# 03_power.net
KiCad netlist of a schematic drawn in Altium Designer
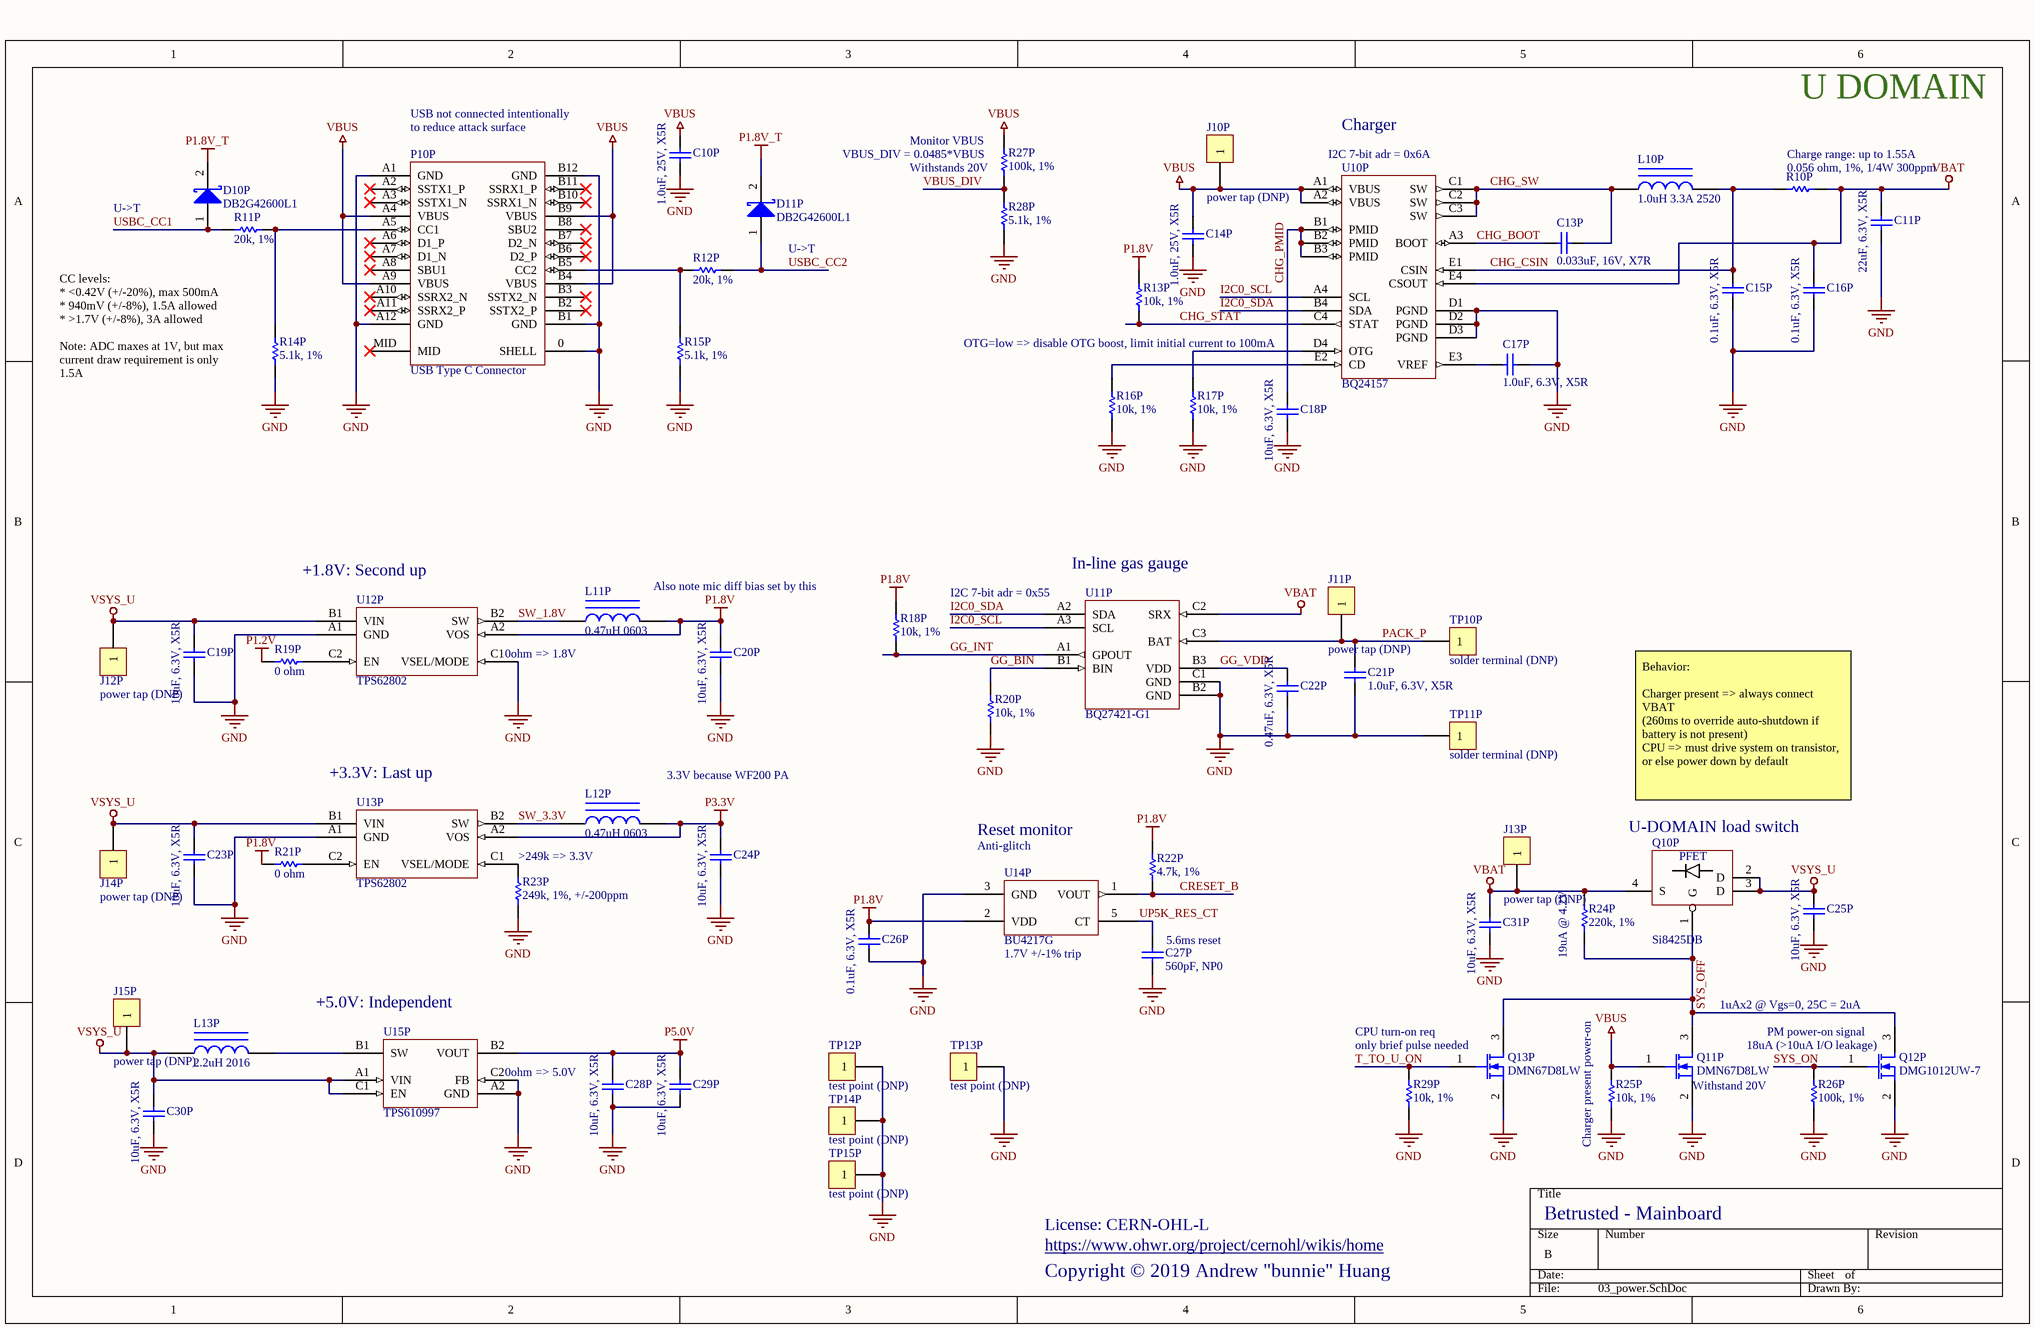
[diagram p0: 03_power.SchDoc]

(export (version "E")
  (design (tool "Eeschema 10.0.6"))
  (components
    (comp (ref "C10P")
      (value "1.0uF, 25V, X5R")
      (footprint "B_CAP0603")
      (description "Capacitor (Semiconductor SIM Model)")
      (fields (field (name "MPN") "CL10A105KA8NNNC"))
      (libsource (lib "Miscellaneous Devices") (part "Cap Semi"))
    )
    (comp (ref "C11P")
      (value "22uF, 6.3V, X5R")
      (footprint "B_CAP0805")
      (description "Capacitor (Semiconductor SIM Model)")
      (fields (field (name "MPN") "CL21A226MQQNNNE"))
      (libsource (lib "Miscellaneous Devices") (part "Cap Semi"))
    )
    (comp (ref "C13P")
      (value "0.033uF, 16V, X7R")
      (footprint "B_RES0402")
      (description "Capacitor (Semiconductor SIM Model)")
      (fields (field (name "MPN") "CL05B333KO5NNNC"))
      (libsource (lib "Miscellaneous Devices") (part "Cap Semi"))
    )
    (comp (ref "C14P")
      (value "1.0uF, 25V, X5R")
      (footprint "B_CAP0603")
      (description "Capacitor (Semiconductor SIM Model)")
      (fields (field (name "MPN") "CL10A105KA8NNNC"))
      (libsource (lib "Miscellaneous Devices") (part "Cap Semi"))
    )
    (comp (ref "C15P")
      (value "0.1uF, 6.3V, X5R")
      (footprint "B_CAP0201")
      (description "Capacitor (Semiconductor SIM Model)")
      (fields (field (name "MPN") "CL03A104KQ3NNNC"))
      (libsource (lib "Miscellaneous Devices") (part "Cap Semi"))
    )
    (comp (ref "C16P")
      (value "0.1uF, 6.3V, X5R")
      (footprint "B_CAP0201")
      (description "Capacitor (Semiconductor SIM Model)")
      (fields (field (name "MPN") "CL03A104KQ3NNNC"))
      (libsource (lib "Miscellaneous Devices") (part "Cap Semi"))
    )
    (comp (ref "C17P")
      (value "1.0uF, 6.3V, X5R")
      (footprint "B_CAP0201")
      (description "Capacitor (Semiconductor SIM Model)")
      (fields (field (name "MPN") "GRM033R60J105MEA2D"))
      (libsource (lib "Miscellaneous Devices") (part "Cap Semi"))
    )
    (comp (ref "C18P")
      (value "10uF, 6.3V, X5R")
      (footprint "B_CAP0603")
      (description "Capacitor (Semiconductor SIM Model)")
      (fields (field (name "MPN") "CL10A106MQ8NNNC"))
      (libsource (lib "Miscellaneous Devices") (part "Cap Semi"))
    )
    (comp (ref "C19P")
      (value "10uF, 6.3V, X5R")
      (footprint "B_CAP0603")
      (description "Capacitor (Semiconductor SIM Model)")
      (fields (field (name "MPN") "CL10A106MQ8NNNC"))
      (libsource (lib "Miscellaneous Devices") (part "Cap Semi"))
    )
    (comp (ref "C20P")
      (value "10uF, 6.3V, X5R")
      (footprint "B_CAP0603")
      (description "Capacitor (Semiconductor SIM Model)")
      (fields (field (name "MPN") "CL10A106MQ8NNNC"))
      (libsource (lib "Miscellaneous Devices") (part "Cap Semi"))
    )
    (comp (ref "C21P")
      (value "1.0uF, 6.3V, X5R")
      (footprint "B_CAP0201")
      (description "Capacitor (Semiconductor SIM Model)")
      (fields (field (name "MPN") "GRM033R60J105MEA2D"))
      (libsource (lib "Miscellaneous Devices") (part "Cap Semi"))
    )
    (comp (ref "C22P")
      (value "0.47uF, 6.3V, X5R")
      (footprint "B_CAP0201")
      (description "Capacitor (Semiconductor SIM Model)")
      (fields (field (name "MPN") "CL03A474KQ3NNNH"))
      (libsource (lib "Miscellaneous Devices") (part "Cap Semi"))
    )
    (comp (ref "C23P")
      (value "10uF, 6.3V, X5R")
      (footprint "B_CAP0603")
      (description "Capacitor (Semiconductor SIM Model)")
      (fields (field (name "MPN") "CL10A106MQ8NNNC"))
      (libsource (lib "Miscellaneous Devices") (part "Cap Semi"))
    )
    (comp (ref "C24P")
      (value "10uF, 6.3V, X5R")
      (footprint "B_CAP0603")
      (description "Capacitor (Semiconductor SIM Model)")
      (fields (field (name "MPN") "CL10A106MQ8NNNC"))
      (libsource (lib "Miscellaneous Devices") (part "Cap Semi"))
    )
    (comp (ref "C25P")
      (value "10uF, 6.3V, X5R")
      (footprint "B_CAP0603")
      (description "Capacitor (Semiconductor SIM Model)")
      (fields (field (name "MPN") "CL10A106MQ8NNNC"))
      (libsource (lib "Miscellaneous Devices") (part "Cap Semi"))
    )
    (comp (ref "C26P")
      (value "0.1uF, 6.3V, X5R")
      (footprint "B_CAP0201")
      (description "Capacitor (Semiconductor SIM Model)")
      (fields (field (name "MPN") "CL03A104KQ3NNNC"))
      (libsource (lib "Miscellaneous Devices") (part "Cap Semi"))
    )
    (comp (ref "C27P")
      (value "560pF, NP0")
      (footprint "B_RES0201")
      (description "Capacitor (Semiconductor SIM Model)")
      (fields (field (name "MPN") "GRM0335C1E561JA01D"))
      (libsource (lib "Miscellaneous Devices") (part "Cap Semi"))
    )
    (comp (ref "C28P")
      (value "10uF, 6.3V, X5R")
      (footprint "B_CAP0603")
      (description "Capacitor (Semiconductor SIM Model)")
      (fields (field (name "MPN") "CL10A106MQ8NNNC"))
      (libsource (lib "Miscellaneous Devices") (part "Cap Semi"))
    )
    (comp (ref "C29P")
      (value "10uF, 6.3V, X5R")
      (footprint "B_CAP0603")
      (description "Capacitor (Semiconductor SIM Model)")
      (fields (field (name "MPN") "CL10A106MQ8NNNC"))
      (libsource (lib "Miscellaneous Devices") (part "Cap Semi"))
    )
    (comp (ref "C30P")
      (value "10uF, 6.3V, X5R")
      (footprint "B_CAP0603")
      (description "Capacitor (Semiconductor SIM Model)")
      (fields (field (name "MPN") "CL10A106MQ8NNNC"))
      (libsource (lib "Miscellaneous Devices") (part "Cap Semi"))
    )
    (comp (ref "C31P")
      (value "10uF, 6.3V, X5R")
      (footprint "B_CAP0603")
      (description "Capacitor (Semiconductor SIM Model)")
      (fields (field (name "MPN") "CL10A106MQ8NNNC"))
      (libsource (lib "Miscellaneous Devices") (part "Cap Semi"))
    )
    (comp (ref "D10P")
      (value "DB2G42600L1")
      (footprint "B_DIO0402")
      (description "Schottky Rectifier")
      (libsource (lib "Miscellaneous Devices") (part "Diode 11DQ03"))
    )
    (comp (ref "D11P")
      (value "DB2G42600L1")
      (footprint "B_DIO0402")
      (description "Schottky Rectifier")
      (libsource (lib "Miscellaneous Devices") (part "Diode 11DQ03"))
    )
    (comp (ref "J10P")
      (value "power tap (DNP)")
      (footprint "RESTAP-0603")
      (description "Connector")
      (fields (field (name "MPN") "DNP"))
      (libsource (lib "") (part "CON1_2"))
    )
    (comp (ref "J11P")
      (value "power tap (DNP)")
      (footprint "RESTAP-0603")
      (description "Connector")
      (fields (field (name "MPN") "DNP"))
      (libsource (lib "") (part "CON1_2"))
    )
    (comp (ref "J12P")
      (value "power tap (DNP)")
      (footprint "RESTAP-0603")
      (description "Connector")
      (fields (field (name "MPN") "DNP"))
      (libsource (lib "") (part "CON1_3"))
    )
    (comp (ref "J13P")
      (value "power tap (DNP)")
      (footprint "RESTAP-0603")
      (description "Connector")
      (fields (field (name "MPN") "DNP"))
      (libsource (lib "") (part "CON1_2"))
    )
    (comp (ref "J14P")
      (value "power tap (DNP)")
      (footprint "RESTAP-0603")
      (description "Connector")
      (fields (field (name "MPN") "DNP"))
      (libsource (lib "") (part "CON1_3"))
    )
    (comp (ref "J15P")
      (value "power tap (DNP)")
      (footprint "RESTAP-0603")
      (description "Connector")
      (fields (field (name "MPN") "DNP"))
      (libsource (lib "") (part "CON1_2"))
    )
    (comp (ref "L10P")
      (value "1.0uH 3.3A 2520")
      (footprint "B_IND2025_SAM")
      (description "Magnetic-Core Inductor")
      (fields (field (name "MPN") "CIGW252010GL1R0MNE"))
      (libsource (lib "Miscellaneous Devices") (part "Inductor Iron"))
    )
    (comp (ref "L11P")
      (value "0.47uH 0603")
      (footprint "B_IND0603")
      (description "Magnetic-Core Inductor")
      (fields (field (name "MPN") "TFM160808ALC-R47MTAA"))
      (libsource (lib "Miscellaneous Devices") (part "Inductor Iron"))
    )
    (comp (ref "L12P")
      (value "0.47uH 0603")
      (footprint "B_IND0603")
      (description "Magnetic-Core Inductor")
      (fields (field (name "MPN") "TFM160808ALC-R47MTAA"))
      (libsource (lib "Miscellaneous Devices") (part "Inductor Iron"))
    )
    (comp (ref "L13P")
      (value "2.2uH 2016")
      (footprint "B_IND2016_TDK")
      (description "Magnetic-Core Inductor")
      (fields (field (name "MPN") "VLS201610CX-2R2M-1"))
      (libsource (lib "Miscellaneous Devices") (part "Inductor Iron"))
    )
    (comp (ref "P10P")
      (value "USB Type C Connector")
      (footprint "HIROSE_CX90B1-24P")
      (fields (field (name "MPN") "CX90B1-24P"))
      (libsource (lib "commonsch-new") (part "USB_TYPE_C"))
    )
    (comp (ref "Q10P")
      (value "Si8425DB")
      (footprint "VISHAY_MICRO_FOOT_4_BUMP")
      (description "P-channel 20V 6.2A 27mOhm @ -2.5V")
      (fields (field (name "MPN") "SI8457DB-T1-E1"))
      (libsource (lib "temp-to-merge") (part "Si8425DB"))
    )
    (comp (ref "Q11P")
      (value "DMN67D8LW")
      (footprint "SOT323-3AN")
      (description "N-Channel MOSFET")
      (fields (field (name "PUBLISHER") "Altium Limited"))
      (libsource (lib "Miscellaneous Devices") (part "MOSFET-N"))
    )
    (comp (ref "Q12P")
      (value "DMG1012UW-7")
      (footprint "SOT323-3AN")
      (description "N-Channel MOSFET")
      (fields (field (name "PUBLISHER") "Altium Limited"))
      (libsource (lib "Miscellaneous Devices") (part "MOSFET-N"))
    )
    (comp (ref "Q13P")
      (value "DMN67D8LW")
      (footprint "SOT323-3AN")
      (description "N-Channel MOSFET")
      (fields (field (name "PUBLISHER") "Altium Limited"))
      (libsource (lib "Miscellaneous Devices") (part "MOSFET-N"))
    )
    (comp (ref "R10P")
      (value "0.056 ohm, 1%, 1/4W 300ppm")
      (footprint "B_RES0402")
      (description "Resistor")
      (fields (field (name "MPN") "ERJ-2BWFR056X"))
      (libsource (lib "Miscellaneous Devices") (part "Res1"))
    )
    (comp (ref "R11P")
      (value "20k, 1%")
      (footprint "B_RES0201")
      (description "Resistor")
      (fields (field (name "MPN") "ANY"))
      (libsource (lib "Miscellaneous Devices") (part "Res1"))
    )
    (comp (ref "R12P")
      (value "20k, 1%")
      (footprint "B_RES0201")
      (description "Resistor")
      (fields (field (name "MPN") "ANY"))
      (libsource (lib "Miscellaneous Devices") (part "Res1"))
    )
    (comp (ref "R13P")
      (value "10k, 1%")
      (footprint "B_RES0201")
      (description "Resistor")
      (fields (field (name "MPN") "ANY"))
      (libsource (lib "Miscellaneous Devices") (part "Res1"))
    )
    (comp (ref "R14P")
      (value "5.1k, 1%")
      (footprint "B_RES0201")
      (description "Resistor")
      (fields (field (name "MPN") "ANY"))
      (libsource (lib "Miscellaneous Devices") (part "Res1"))
    )
    (comp (ref "R15P")
      (value "5.1k, 1%")
      (footprint "B_RES0201")
      (description "Resistor")
      (fields (field (name "MPN") "ANY"))
      (libsource (lib "Miscellaneous Devices") (part "Res1"))
    )
    (comp (ref "R16P")
      (value "10k, 1%")
      (footprint "B_RES0201")
      (description "Resistor")
      (fields (field (name "MPN") "ANY"))
      (libsource (lib "Miscellaneous Devices") (part "Res1"))
    )
    (comp (ref "R17P")
      (value "10k, 1%")
      (footprint "B_RES0201")
      (description "Resistor")
      (fields (field (name "MPN") "ANY"))
      (libsource (lib "Miscellaneous Devices") (part "Res1"))
    )
    (comp (ref "R18P")
      (value "10k, 1%")
      (footprint "B_RES0201")
      (description "Resistor")
      (fields (field (name "MPN") "ANY"))
      (libsource (lib "Miscellaneous Devices") (part "Res1"))
    )
    (comp (ref "R19P")
      (value "0 ohm")
      (footprint "B_RES0201")
      (description "Resistor")
      (fields (field (name "MPN") "ANY"))
      (libsource (lib "Miscellaneous Devices") (part "Res1"))
    )
    (comp (ref "R20P")
      (value "10k, 1%")
      (footprint "B_RES0201")
      (description "Resistor")
      (fields (field (name "MPN") "ANY"))
      (libsource (lib "Miscellaneous Devices") (part "Res1"))
    )
    (comp (ref "R21P")
      (value "0 ohm")
      (footprint "B_RES0201")
      (description "Resistor")
      (fields (field (name "MPN") "ANY"))
      (libsource (lib "Miscellaneous Devices") (part "Res1"))
    )
    (comp (ref "R22P")
      (value "4.7k, 1%")
      (footprint "B_RES0201")
      (description "Resistor")
      (fields (field (name "MPN") "ANY"))
      (libsource (lib "Miscellaneous Devices") (part "Res1"))
    )
    (comp (ref "R23P")
      (value "249k, 1%, +/-200ppm")
      (footprint "B_RES0402")
      (description "Resistor")
      (fields (field (name "MPN") "RC0402FR-07249KL"))
      (libsource (lib "Miscellaneous Devices") (part "Res1"))
    )
    (comp (ref "R24P")
      (value "220k, 1%")
      (footprint "B_RES0201")
      (description "Resistor")
      (fields (field (name "MPN") "ANY"))
      (libsource (lib "Miscellaneous Devices") (part "Res1"))
    )
    (comp (ref "R25P")
      (value "10k, 1%")
      (footprint "B_RES0201")
      (description "Resistor")
      (fields (field (name "MPN") "ANY"))
      (libsource (lib "Miscellaneous Devices") (part "Res1"))
    )
    (comp (ref "R26P")
      (value "100k, 1%")
      (footprint "B_RES0201")
      (description "Resistor")
      (fields (field (name "MPN") "ANY"))
      (libsource (lib "Miscellaneous Devices") (part "Res1"))
    )
    (comp (ref "R27P")
      (value "100k, 1%")
      (footprint "B_RES0201")
      (description "Resistor")
      (fields (field (name "MPN") "ANY"))
      (libsource (lib "Miscellaneous Devices") (part "Res1"))
    )
    (comp (ref "R28P")
      (value "5.1k, 1%")
      (footprint "B_RES0201")
      (description "Resistor")
      (fields (field (name "MPN") "ANY"))
      (libsource (lib "Miscellaneous Devices") (part "Res1"))
    )
    (comp (ref "R29P")
      (value "10k, 1%")
      (footprint "B_RES0201")
      (description "Resistor")
      (fields (field (name "MPN") "ANY"))
      (libsource (lib "Miscellaneous Devices") (part "Res1"))
    )
    (comp (ref "TP10P")
      (value "solder terminal (DNP)")
      (footprint "55-MIL-HOLE")
      (description "Connector")
      (fields (field (name "MPN") "DNP"))
      (libsource (lib "*") (part "CON1"))
    )
    (comp (ref "TP11P")
      (value "solder terminal (DNP)")
      (footprint "55-MIL-HOLE")
      (description "Connector")
      (fields (field (name "MPN") "DNP"))
      (libsource (lib "*") (part "CON1"))
    )
    (comp (ref "TP12P")
      (value "test point (DNP)")
      (footprint "TP_2MM_SQ")
      (description "Connector")
      (fields (field (name "MPN") "DNP"))
      (libsource (lib "") (part "CON1_1"))
    )
    (comp (ref "TP13P")
      (value "test point (DNP)")
      (footprint "TP_2MM_SQ")
      (description "Connector")
      (fields (field (name "MPN") "DNP"))
      (libsource (lib "") (part "CON1_1"))
    )
    (comp (ref "TP14P")
      (value "test point (DNP)")
      (footprint "TP_2MM_SQ")
      (description "Connector")
      (fields (field (name "MPN") "DNP"))
      (libsource (lib "") (part "CON1_1"))
    )
    (comp (ref "TP15P")
      (value "test point (DNP)")
      (footprint "TP_2MM_SQ")
      (description "Connector")
      (fields (field (name "MPN") "DNP"))
      (libsource (lib "") (part "CON1_1"))
    )
    (comp (ref "U10P")
      (value "BQ24157")
      (footprint "BGA20C40P4X5_200X214X62")
      (description "Fully integrated switch-mode charger with USB compliance and OTG support")
      (fields (field (name "MPN") "BQ24157YFFR"))
      (libsource (lib "altium-import") (part "root_0_BQ24157_"))
    )
    (comp (ref "U11P")
      (value "BQ27421-G1")
      (footprint "BGA9C50P3X3_162X158X62")
      (description "System-Side Impedance Track Fuel Gauge with integrated Sense Resistor")
      (fields (field (name "MPN") "bq27421YZFT-G1A"))
      (libsource (lib "altium-import") (part "root_0_BQ27421-G1_"))
    )
    (comp (ref "U12P")
      (value "TPS62802")
      (footprint "BGA6C35P2X3_70X105X40_NSMD")
      (description "Buck regulator, 4MHz, 0.6A, 1.8V-3.3V, low Iq")
      (fields (field (name "MPN") "TPS62802YKAR"))
      (libsource (lib "altium-import") (part "root_0_TPS62802_"))
    )
    (comp (ref "U13P")
      (value "TPS62802")
      (footprint "BGA6C35P2X3_70X105X40_NSMD")
      (description "Buck regulator, 4MHz, 0.6A, 1.8V-3.3V, low Iq")
      (fields (field (name "MPN") "TPS62802YKAR"))
      (libsource (lib "altium-import") (part "root_0_TPS62802_"))
    )
    (comp (ref "U14P")
      (value "BU4217G")
      (footprint "SOT23-5AN")
      (description "Low voltage free delay time setting CMOS voltage detector IC")
      (fields (field (name "MPN") "BU4217G-TR"))
      (libsource (lib "commonsch-new") (part "BU42XXG"))
    )
    (comp (ref "U15P")
      (value "TPS610997")
      (footprint "BGA6C40P2X3_88X123X62")
      (description "Synchronous Boost Converter with Ultra-Low Iq")
      (fields (field (name "MPN") "TPS610997YFFR"))
      (libsource (lib "altium-import") (part "root_0_TPS610997_"))
    )
  )
  (nets
    (net (code "1") (name "/CHG_BOOT") (class "Default")
      (node (ref "C13P") (pin "2") (pinfunction "2_2") (pintype "passive"))
      (node (ref "U10P") (pin "A3") (pinfunction "BOOT_A3") (pintype "bidirectional"))
    )
    (net (code "2") (name "/CHG_CSIN") (class "Default")
      (node (ref "C15P") (pin "1") (pinfunction "1_1") (pintype "passive"))
      (node (ref "L10P") (pin "2") (pinfunction "2_2") (pintype "passive"))
      (node (ref "R10P") (pin "2") (pinfunction "2_2") (pintype "passive"))
      (node (ref "U10P") (pin "E1") (pinfunction "CSIN_E1") (pintype "input"))
    )
    (net (code "3") (name "/CHG_PMID") (class "Default")
      (node (ref "C18P") (pin "1") (pinfunction "1_1") (pintype "passive"))
      (node (ref "U10P") (pin "B1") (pinfunction "PMID_B1") (pintype "bidirectional"))
      (node (ref "U10P") (pin "B2") (pinfunction "PMID_B2") (pintype "bidirectional"))
      (node (ref "U10P") (pin "B3") (pinfunction "PMID_B3") (pintype "bidirectional"))
    )
    (net (code "4") (name "/CHG_STAT") (class "Default")
      (node (ref "R13P") (pin "2") (pinfunction "2_2") (pintype "passive"))
      (node (ref "U10P") (pin "C4") (pinfunction "STAT_C4") (pintype "output"))
    )
    (net (code "5") (name "/CHG_SW") (class "Default")
      (node (ref "C13P") (pin "1") (pinfunction "1_1") (pintype "passive"))
      (node (ref "L10P") (pin "1") (pinfunction "1_1") (pintype "passive"))
      (node (ref "U10P") (pin "C1") (pinfunction "SW_C1") (pintype "output"))
      (node (ref "U10P") (pin "C2") (pinfunction "SW_C2") (pintype "output"))
      (node (ref "U10P") (pin "C3") (pinfunction "SW_C3") (pintype "output"))
    )
    (net (code "6") (name "/CRESET_B") (class "Default")
      (node (ref "R22P") (pin "1") (pinfunction "1_1") (pintype "passive"))
      (node (ref "U14P") (pin "1") (pinfunction "VOUT_1") (pintype "output"))
    )
    (net (code "7") (name "/GG_BIN") (class "Default")
      (node (ref "R20P") (pin "1") (pinfunction "1_1") (pintype "passive"))
      (node (ref "U11P") (pin "B1") (pinfunction "BIN_B1") (pintype "input"))
    )
    (net (code "8") (name "/GG_INT") (class "Default")
      (node (ref "R18P") (pin "2") (pinfunction "2_2") (pintype "passive"))
      (node (ref "U11P") (pin "A1") (pinfunction "GPOUT_A1") (pintype "output"))
    )
    (net (code "9") (name "/GG_VDD") (class "Default")
      (node (ref "C22P") (pin "1") (pinfunction "1_1") (pintype "passive"))
      (node (ref "U11P") (pin "B3") (pinfunction "VDD_B3") (pintype "power_in"))
    )
    (net (code "10") (name "/I2C0_SCL") (class "Default")
      (node (ref "U10P") (pin "A4") (pinfunction "SCL_A4") (pintype "open_collector"))
      (node (ref "U11P") (pin "A3") (pinfunction "SCL_A3") (pintype "open_collector"))
    )
    (net (code "11") (name "/I2C0_SDA") (class "Default")
      (node (ref "U10P") (pin "B4") (pinfunction "SDA_B4") (pintype "open_collector"))
      (node (ref "U11P") (pin "A2") (pinfunction "SDA_A2") (pintype "open_collector"))
    )
    (net (code "12") (name "/PACK_P") (class "Default")
      (node (ref "C21P") (pin "2") (pinfunction "2_2") (pintype "passive"))
      (node (ref "J11P") (pin "1") (pinfunction "1_1") (pintype "passive"))
      (node (ref "TP10P") (pin "1") (pinfunction "1_1") (pintype "passive"))
      (node (ref "U11P") (pin "C3") (pinfunction "BAT_C3") (pintype "input"))
    )
    (net (code "13") (name "/SW_1.8V") (class "Default")
      (node (ref "L11P") (pin "1") (pinfunction "1_1") (pintype "passive"))
      (node (ref "U12P") (pin "B2") (pinfunction "SW_B2") (pintype "output"))
    )
    (net (code "14") (name "/SW_3.3V") (class "Default")
      (node (ref "L12P") (pin "1") (pinfunction "1_1") (pintype "passive"))
      (node (ref "U13P") (pin "B2") (pinfunction "SW_B2") (pintype "output"))
    )
    (net (code "15") (name "/SYS_OFF") (class "Default")
      (node (ref "Q10P") (pin "1") (pinfunction "G_1") (pintype "passive"))
      (node (ref "Q11P") (pin "3") (pinfunction "D_3") (pintype "passive"))
      (node (ref "Q12P") (pin "3") (pinfunction "D_3") (pintype "passive"))
      (node (ref "Q13P") (pin "3") (pinfunction "D_3") (pintype "passive"))
      (node (ref "R24P") (pin "1") (pinfunction "1_1") (pintype "passive"))
    )
    (net (code "16") (name "/SYS_ON") (class "Default")
      (node (ref "Q12P") (pin "1") (pinfunction "G_1") (pintype "passive"))
      (node (ref "R26P") (pin "2") (pinfunction "2_2") (pintype "passive"))
    )
    (net (code "17") (name "/T_TO_U_ON") (class "Default")
      (node (ref "Q13P") (pin "1") (pinfunction "G_1") (pintype "passive"))
      (node (ref "R29P") (pin "1") (pinfunction "1_1") (pintype "passive"))
    )
    (net (code "18") (name "/UP5K_RES_CT") (class "Default")
      (node (ref "C27P") (pin "1") (pinfunction "1_1") (pintype "passive"))
      (node (ref "U14P") (pin "5") (pinfunction "CT_5") (pintype "passive"))
    )
    (net (code "19") (name "/USBC_CC1") (class "Default")
      (node (ref "D10P") (pin "1") (pinfunction "A_1") (pintype "passive"))
      (node (ref "R11P") (pin "2") (pinfunction "2_2") (pintype "passive"))
    )
    (net (code "20") (name "/USBC_CC2") (class "Default")
      (node (ref "D11P") (pin "1") (pinfunction "A_1") (pintype "passive"))
      (node (ref "R12P") (pin "1") (pinfunction "1_1") (pintype "passive"))
    )
    (net (code "21") (name "/VBUS_DIV") (class "Default")
      (node (ref "R27P") (pin "1") (pinfunction "1_1") (pintype "passive"))
      (node (ref "R28P") (pin "1") (pinfunction "1_1") (pintype "passive"))
    )
    (net (code "22") (name "GND") (class "Default")
      (node (ref "C10P") (pin "2") (pinfunction "2_2") (pintype "passive"))
      (node (ref "C11P") (pin "2") (pinfunction "2_2") (pintype "passive"))
      (node (ref "C14P") (pin "2") (pinfunction "2_2") (pintype "passive"))
      (node (ref "C15P") (pin "2") (pinfunction "2_2") (pintype "passive"))
      (node (ref "C16P") (pin "2") (pinfunction "2_2") (pintype "passive"))
      (node (ref "C17P") (pin "2") (pinfunction "2_2") (pintype "passive"))
      (node (ref "C18P") (pin "2") (pinfunction "2_2") (pintype "passive"))
      (node (ref "C19P") (pin "2") (pinfunction "2_2") (pintype "passive"))
      (node (ref "C20P") (pin "2") (pinfunction "2_2") (pintype "passive"))
      (node (ref "C21P") (pin "1") (pinfunction "1_1") (pintype "passive"))
      (node (ref "C22P") (pin "2") (pinfunction "2_2") (pintype "passive"))
      (node (ref "C23P") (pin "2") (pinfunction "2_2") (pintype "passive"))
      (node (ref "C24P") (pin "2") (pinfunction "2_2") (pintype "passive"))
      (node (ref "C25P") (pin "2") (pinfunction "2_2") (pintype "passive"))
      (node (ref "C26P") (pin "2") (pinfunction "2_2") (pintype "passive"))
      (node (ref "C27P") (pin "2") (pinfunction "2_2") (pintype "passive"))
      (node (ref "C28P") (pin "2") (pinfunction "2_2") (pintype "passive"))
      (node (ref "C29P") (pin "2") (pinfunction "2_2") (pintype "passive"))
      (node (ref "C30P") (pin "2") (pinfunction "2_2") (pintype "passive"))
      (node (ref "C31P") (pin "2") (pinfunction "2_2") (pintype "passive"))
      (node (ref "P10P") (pin "0") (pinfunction "SHELL_0") (pintype "passive"))
      (node (ref "P10P") (pin "A1") (pinfunction "GND_A1") (pintype "power_in"))
      (node (ref "P10P") (pin "A12") (pinfunction "GND_A12") (pintype "power_in"))
      (node (ref "P10P") (pin "B1") (pinfunction "GND_B1") (pintype "power_in"))
      (node (ref "P10P") (pin "B12") (pinfunction "GND_B12") (pintype "power_in"))
      (node (ref "Q11P") (pin "2") (pinfunction "S_2") (pintype "passive"))
      (node (ref "Q12P") (pin "2") (pinfunction "S_2") (pintype "passive"))
      (node (ref "Q13P") (pin "2") (pinfunction "S_2") (pintype "passive"))
      (node (ref "R14P") (pin "2") (pinfunction "2_2") (pintype "passive"))
      (node (ref "R15P") (pin "2") (pinfunction "2_2") (pintype "passive"))
      (node (ref "R16P") (pin "2") (pinfunction "2_2") (pintype "passive"))
      (node (ref "R17P") (pin "2") (pinfunction "2_2") (pintype "passive"))
      (node (ref "R20P") (pin "2") (pinfunction "2_2") (pintype "passive"))
      (node (ref "R23P") (pin "2") (pinfunction "2_2") (pintype "passive"))
      (node (ref "R25P") (pin "2") (pinfunction "2_2") (pintype "passive"))
      (node (ref "R26P") (pin "1") (pinfunction "1_1") (pintype "passive"))
      (node (ref "R28P") (pin "2") (pinfunction "2_2") (pintype "passive"))
      (node (ref "R29P") (pin "2") (pinfunction "2_2") (pintype "passive"))
      (node (ref "TP11P") (pin "1") (pinfunction "1_1") (pintype "passive"))
      (node (ref "TP12P") (pin "1") (pinfunction "1_1") (pintype "passive"))
      (node (ref "TP13P") (pin "1") (pinfunction "1_1") (pintype "passive"))
      (node (ref "TP14P") (pin "1") (pinfunction "1_1") (pintype "passive"))
      (node (ref "TP15P") (pin "1") (pinfunction "1_1") (pintype "passive"))
      (node (ref "U10P") (pin "D1") (pinfunction "PGND_D1") (pintype "power_in"))
      (node (ref "U10P") (pin "D2") (pinfunction "PGND_D2") (pintype "power_in"))
      (node (ref "U10P") (pin "D3") (pinfunction "PGND_D3") (pintype "power_in"))
      (node (ref "U11P") (pin "B2") (pinfunction "GND_B2") (pintype "power_in"))
      (node (ref "U11P") (pin "C1") (pinfunction "GND_C1") (pintype "power_in"))
      (node (ref "U12P") (pin "A1") (pinfunction "GND_A1") (pintype "power_in"))
      (node (ref "U12P") (pin "C1") (pinfunction "VSEL/MODE_C1") (pintype "input"))
      (node (ref "U13P") (pin "A1") (pinfunction "GND_A1") (pintype "power_in"))
      (node (ref "U14P") (pin "3") (pinfunction "GND_3") (pintype "power_in"))
      (node (ref "U15P") (pin "A2") (pinfunction "GND_A2") (pintype "power_in"))
      (node (ref "U15P") (pin "C2") (pinfunction "FB_C2") (pintype "input"))
    )
    (net (code "23") (name "Net-(P10P-CC1)") (class "Default")
      (node (ref "P10P") (pin "A5") (pinfunction "CC1_A5") (pintype "bidirectional"))
      (node (ref "R11P") (pin "1") (pinfunction "1_1") (pintype "passive"))
      (node (ref "R14P") (pin "1") (pinfunction "1_1") (pintype "passive"))
    )
    (net (code "24") (name "Net-(P10P-CC2)") (class "Default")
      (node (ref "P10P") (pin "B5") (pinfunction "CC2_B5") (pintype "bidirectional"))
      (node (ref "R12P") (pin "2") (pinfunction "2_2") (pintype "passive"))
      (node (ref "R15P") (pin "1") (pinfunction "1_1") (pintype "passive"))
    )
    (net (code "25") (name "Net-(U10P-CD)") (class "Default")
      (node (ref "R16P") (pin "1") (pinfunction "1_1") (pintype "passive"))
      (node (ref "U10P") (pin "E2") (pinfunction "CD_E2") (pintype "input"))
    )
    (net (code "26") (name "Net-(U10P-OTG)") (class "Default")
      (node (ref "R17P") (pin "1") (pinfunction "1_1") (pintype "passive"))
      (node (ref "U10P") (pin "D4") (pinfunction "OTG_D4") (pintype "input"))
    )
    (net (code "27") (name "Net-(U10P-VREF)") (class "Default")
      (node (ref "C17P") (pin "1") (pinfunction "1_1") (pintype "passive"))
      (node (ref "U10P") (pin "E3") (pinfunction "VREF_E3") (pintype "output"))
    )
    (net (code "28") (name "Net-(U12P-EN)") (class "Default")
      (node (ref "R19P") (pin "2") (pinfunction "2_2") (pintype "passive"))
      (node (ref "U12P") (pin "C2") (pinfunction "EN_C2") (pintype "input"))
    )
    (net (code "29") (name "Net-(U13P-EN)") (class "Default")
      (node (ref "R21P") (pin "2") (pinfunction "2_2") (pintype "passive"))
      (node (ref "U13P") (pin "C2") (pinfunction "EN_C2") (pintype "input"))
    )
    (net (code "30") (name "Net-(U13P-VSEL{slash}MODE)") (class "Default")
      (node (ref "R23P") (pin "1") (pinfunction "1_1") (pintype "passive"))
      (node (ref "U13P") (pin "C1") (pinfunction "VSEL/MODE_C1") (pintype "input"))
    )
    (net (code "31") (name "Net-(U15P-SW)") (class "Default")
      (node (ref "L13P") (pin "2") (pinfunction "2_2") (pintype "passive"))
      (node (ref "U15P") (pin "B1") (pinfunction "SW_B1") (pintype "power_in"))
    )
    (net (code "32") (name "P1.2V") (class "Default")
      (node (ref "R19P") (pin "1") (pinfunction "1_1") (pintype "passive"))
    )
    (net (code "33") (name "P1.8V") (class "Default")
      (node (ref "C20P") (pin "1") (pinfunction "1_1") (pintype "passive"))
      (node (ref "C26P") (pin "1") (pinfunction "1_1") (pintype "passive"))
      (node (ref "L11P") (pin "2") (pinfunction "2_2") (pintype "passive"))
      (node (ref "R13P") (pin "1") (pinfunction "1_1") (pintype "passive"))
      (node (ref "R18P") (pin "1") (pinfunction "1_1") (pintype "passive"))
      (node (ref "R21P") (pin "1") (pinfunction "1_1") (pintype "passive"))
      (node (ref "R22P") (pin "2") (pinfunction "2_2") (pintype "passive"))
      (node (ref "U12P") (pin "A2") (pinfunction "VOS_A2") (pintype "input"))
      (node (ref "U14P") (pin "2") (pinfunction "VDD_2") (pintype "power_in"))
    )
    (net (code "34") (name "P1.8V_T") (class "Default")
      (node (ref "D10P") (pin "2") (pinfunction "K_2") (pintype "passive"))
      (node (ref "D11P") (pin "2") (pinfunction "K_2") (pintype "passive"))
    )
    (net (code "35") (name "P3.3V") (class "Default")
      (node (ref "C24P") (pin "1") (pinfunction "1_1") (pintype "passive"))
      (node (ref "L12P") (pin "2") (pinfunction "2_2") (pintype "passive"))
      (node (ref "U13P") (pin "A2") (pinfunction "VOS_A2") (pintype "input"))
    )
    (net (code "36") (name "P5.0V") (class "Default")
      (node (ref "C28P") (pin "1") (pinfunction "1_1") (pintype "passive"))
      (node (ref "C29P") (pin "1") (pinfunction "1_1") (pintype "passive"))
      (node (ref "U15P") (pin "B2") (pinfunction "VOUT_B2") (pintype "power_in"))
    )
    (net (code "37") (name "VBAT") (class "Default")
      (node (ref "C11P") (pin "1") (pinfunction "1_1") (pintype "passive"))
      (node (ref "C16P") (pin "1") (pinfunction "1_1") (pintype "passive"))
      (node (ref "C31P") (pin "1") (pinfunction "1_1") (pintype "passive"))
      (node (ref "J13P") (pin "1") (pinfunction "1_1") (pintype "passive"))
      (node (ref "Q10P") (pin "4") (pinfunction "S_4") (pintype "passive"))
      (node (ref "R10P") (pin "1") (pinfunction "1_1") (pintype "passive"))
      (node (ref "R24P") (pin "2") (pinfunction "2_2") (pintype "passive"))
      (node (ref "U10P") (pin "E4") (pinfunction "CSOUT_E4") (pintype "input"))
      (node (ref "U11P") (pin "C2") (pinfunction "SRX_C2") (pintype "input"))
    )
    (net (code "38") (name "VBUS") (class "Default")
      (node (ref "C10P") (pin "1") (pinfunction "1_1") (pintype "passive"))
      (node (ref "C14P") (pin "1") (pinfunction "1_1") (pintype "passive"))
      (node (ref "J10P") (pin "1") (pinfunction "1_1") (pintype "passive"))
      (node (ref "P10P") (pin "A4") (pinfunction "VBUS_A4") (pintype "power_in"))
      (node (ref "P10P") (pin "A9") (pinfunction "VBUS_A9") (pintype "power_in"))
      (node (ref "P10P") (pin "B4") (pinfunction "VBUS_B4") (pintype "power_in"))
      (node (ref "P10P") (pin "B9") (pinfunction "VBUS_B9") (pintype "power_in"))
      (node (ref "Q11P") (pin "1") (pinfunction "G_1") (pintype "passive"))
      (node (ref "R25P") (pin "1") (pinfunction "1_1") (pintype "passive"))
      (node (ref "R27P") (pin "2") (pinfunction "2_2") (pintype "passive"))
      (node (ref "U10P") (pin "A1") (pinfunction "VBUS_A1") (pintype "bidirectional"))
      (node (ref "U10P") (pin "A2") (pinfunction "VBUS_A2") (pintype "bidirectional"))
    )
    (net (code "39") (name "VSYS_U") (class "Default")
      (node (ref "C19P") (pin "1") (pinfunction "1_1") (pintype "passive"))
      (node (ref "C23P") (pin "1") (pinfunction "1_1") (pintype "passive"))
      (node (ref "C25P") (pin "1") (pinfunction "1_1") (pintype "passive"))
      (node (ref "C30P") (pin "1") (pinfunction "1_1") (pintype "passive"))
      (node (ref "J12P") (pin "1") (pinfunction "1_1") (pintype "passive"))
      (node (ref "J14P") (pin "1") (pinfunction "1_1") (pintype "passive"))
      (node (ref "J15P") (pin "1") (pinfunction "1_1") (pintype "passive"))
      (node (ref "L13P") (pin "1") (pinfunction "1_1") (pintype "passive"))
      (node (ref "Q10P") (pin "2") (pinfunction "D_2") (pintype "passive"))
      (node (ref "Q10P") (pin "3") (pinfunction "D_3") (pintype "passive"))
      (node (ref "U12P") (pin "B1") (pinfunction "VIN_B1") (pintype "power_in"))
      (node (ref "U13P") (pin "B1") (pinfunction "VIN_B1") (pintype "power_in"))
      (node (ref "U15P") (pin "A1") (pinfunction "VIN_A1") (pintype "input"))
      (node (ref "U15P") (pin "C1") (pinfunction "EN_C1") (pintype "input"))
    )
    (net (code "40") (name "unconnected-(P10P-D1_N-PadA7)") (class "Default")
      (node (ref "P10P") (pin "A7") (pinfunction "D1_N_A7") (pintype "bidirectional+no_connect"))
    )
    (net (code "41") (name "unconnected-(P10P-D1_P-PadA6)") (class "Default")
      (node (ref "P10P") (pin "A6") (pinfunction "D1_P_A6") (pintype "bidirectional+no_connect"))
    )
    (net (code "42") (name "unconnected-(P10P-D2_N-PadB7)") (class "Default")
      (node (ref "P10P") (pin "B7") (pinfunction "D2_N_B7") (pintype "bidirectional+no_connect"))
    )
    (net (code "43") (name "unconnected-(P10P-D2_P-PadB6)") (class "Default")
      (node (ref "P10P") (pin "B6") (pinfunction "D2_P_B6") (pintype "bidirectional+no_connect"))
    )
    (net (code "44") (name "unconnected-(P10P-PadMID)") (class "Default")
      (node (ref "P10P") (pin "MID") (pinfunction "MID_MID") (pintype "passive+no_connect"))
    )
    (net (code "45") (name "unconnected-(P10P-SBU1-PadA8)") (class "Default")
      (node (ref "P10P") (pin "A8") (pinfunction "SBU1_A8") (pintype "passive+no_connect"))
    )
    (net (code "46") (name "unconnected-(P10P-SBU2-PadB8)") (class "Default")
      (node (ref "P10P") (pin "B8") (pinfunction "SBU2_B8") (pintype "passive+no_connect"))
    )
    (net (code "47") (name "unconnected-(P10P-SSRX1_N-PadB10)") (class "Default")
      (node (ref "P10P") (pin "B10") (pinfunction "SSRX1_N_B10") (pintype "bidirectional+no_connect"))
    )
    (net (code "48") (name "unconnected-(P10P-SSRX1_P-PadB11)") (class "Default")
      (node (ref "P10P") (pin "B11") (pinfunction "SSRX1_P_B11") (pintype "bidirectional+no_connect"))
    )
    (net (code "49") (name "unconnected-(P10P-SSRX2_N-PadA10)") (class "Default")
      (node (ref "P10P") (pin "A10") (pinfunction "SSRX2_N_A10") (pintype "bidirectional+no_connect"))
    )
    (net (code "50") (name "unconnected-(P10P-SSRX2_P-PadA11)") (class "Default")
      (node (ref "P10P") (pin "A11") (pinfunction "SSRX2_P_A11") (pintype "bidirectional+no_connect"))
    )
    (net (code "51") (name "unconnected-(P10P-SSTX1_N-PadA3)") (class "Default")
      (node (ref "P10P") (pin "A3") (pinfunction "SSTX1_N_A3") (pintype "bidirectional+no_connect"))
    )
    (net (code "52") (name "unconnected-(P10P-SSTX1_P-PadA2)") (class "Default")
      (node (ref "P10P") (pin "A2") (pinfunction "SSTX1_P_A2") (pintype "bidirectional+no_connect"))
    )
    (net (code "53") (name "unconnected-(P10P-SSTX2_N-PadB3)") (class "Default")
      (node (ref "P10P") (pin "B3") (pinfunction "SSTX2_N_B3") (pintype "power_in+no_connect"))
    )
    (net (code "54") (name "unconnected-(P10P-SSTX2_P-PadB2)") (class "Default")
      (node (ref "P10P") (pin "B2") (pinfunction "SSTX2_P_B2") (pintype "power_in+no_connect"))
    )
  )
)
